# 01_MAIN.net
KiCad netlist of a schematic drawn in Altium Designer
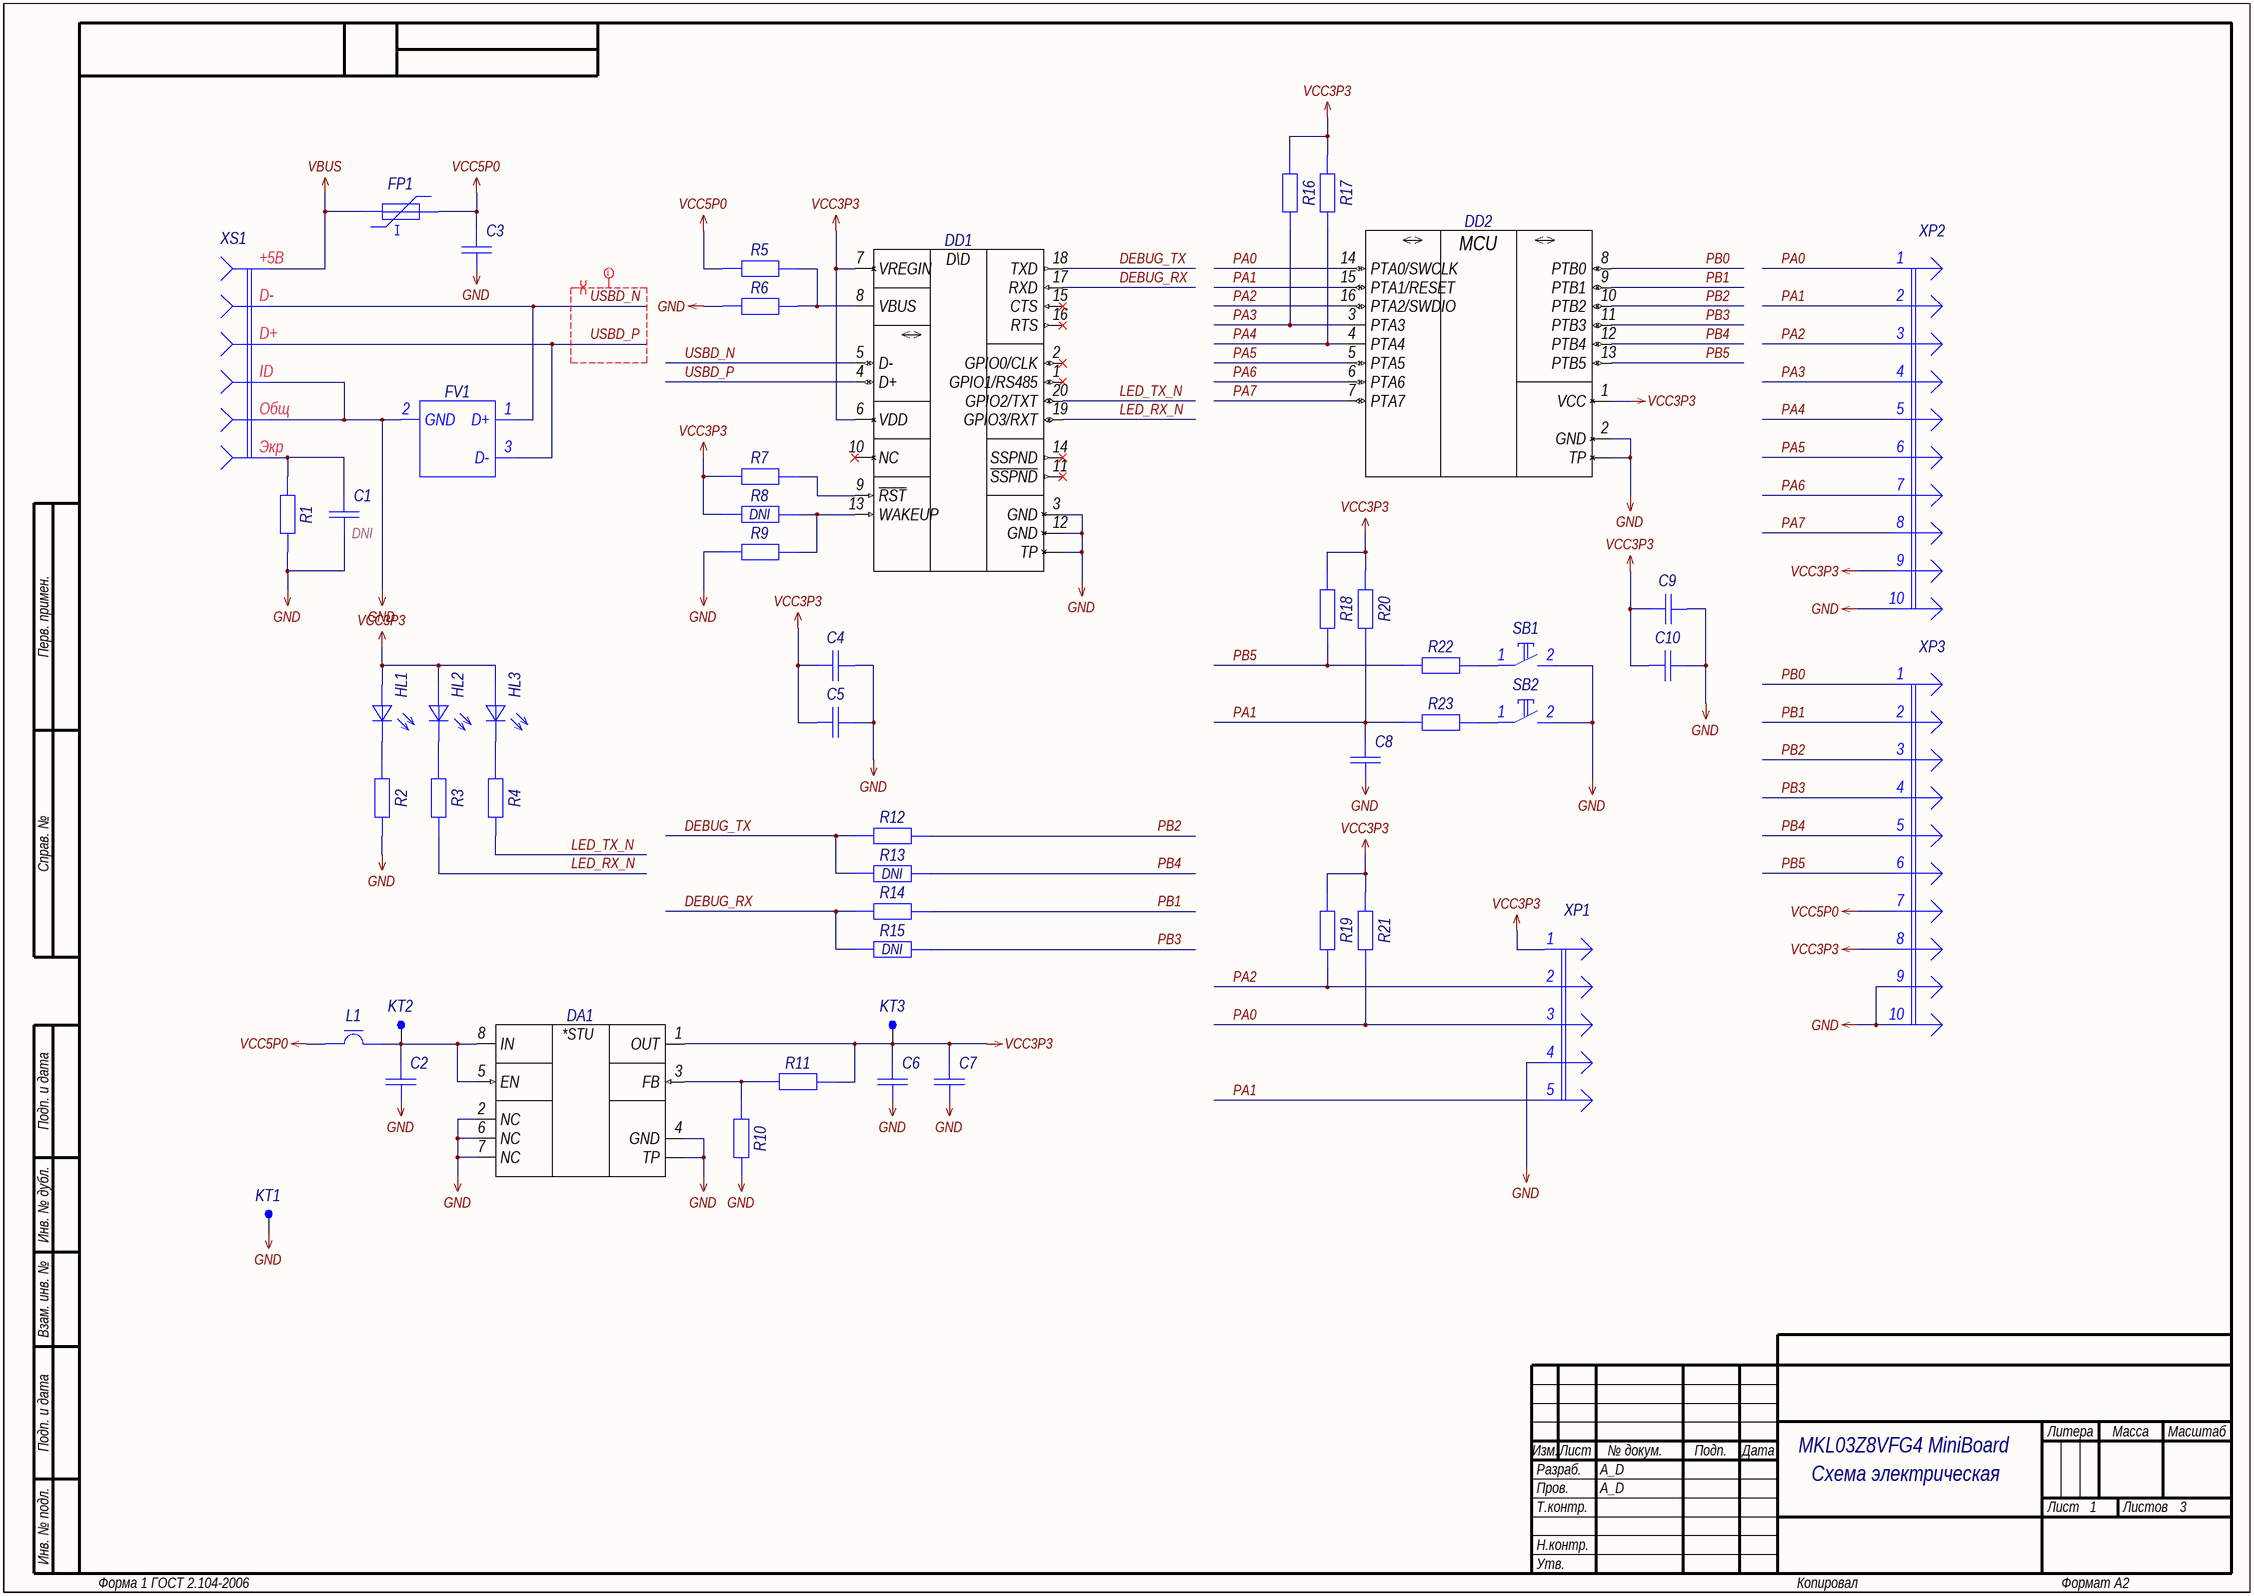
[diagram p0: 01_MAIN.SchDoc]

(export (version "E")
  (design (tool "Eeschema 10.0.6"))
  (components
    (comp (ref "C1")
      (value "Capacitor")
      (footprint "C0603_L")
      (fields
        (field (name "PART NUMBER") "GRM188R72A104KA35D")
        (field (name "VOLTAGE") "100V")
        (field (name "TOLERANCE") "±10%")
        (field (name "PUBLISHER") "Andrew Danich")
      )
      (libsource (lib "ADLib") (part "Capacitor"))
    )
    (comp (ref "C2")
      (value "Capacitor")
      (footprint "C0402_L")
      (fields
        (field (name "PART NUMBER") "GRM155R60J475ME87D")
        (field (name "VOLTAGE") "6.3V")
        (field (name "TOLERANCE") "±20%")
        (field (name "PUBLISHER") "Andrew Danich")
      )
      (libsource (lib "ADLib") (part "Capacitor"))
    )
    (comp (ref "C3")
      (value "Capacitor")
      (footprint "C0603_L")
      (fields
        (field (name "PART NUMBER") "GRM188R60J106ME47D")
        (field (name "VOLTAGE") "6.3V")
        (field (name "TOLERANCE") "±20%")
        (field (name "PUBLISHER") "Andrew Danich")
      )
      (libsource (lib "ADLib") (part "Capacitor"))
    )
    (comp (ref "C4")
      (value "Capacitor")
      (footprint "C0402_L")
      (fields
        (field (name "PART NUMBER") "GRM155R60J475ME87D")
        (field (name "VOLTAGE") "6.3V")
        (field (name "TOLERANCE") "±20%")
        (field (name "PUBLISHER") "Andrew Danich")
      )
      (libsource (lib "ADLib") (part "Capacitor"))
    )
    (comp (ref "C5")
      (value "Capacitor")
      (footprint "C0402_L")
      (fields
        (field (name "PART NUMBER") "GRM155R60J475ME87D")
        (field (name "VOLTAGE") "6.3V")
        (field (name "TOLERANCE") "±20%")
        (field (name "PUBLISHER") "Andrew Danich")
      )
      (libsource (lib "ADLib") (part "Capacitor"))
    )
    (comp (ref "C6")
      (value "Capacitor")
      (footprint "C0402_L")
      (fields
        (field (name "PART NUMBER") "GRM155R60J475ME87D")
        (field (name "VOLTAGE") "6.3V")
        (field (name "TOLERANCE") "±20%")
        (field (name "PUBLISHER") "Andrew Danich")
      )
      (libsource (lib "ADLib") (part "Capacitor"))
    )
    (comp (ref "C7")
      (value "Capacitor")
      (footprint "C0402_L")
      (fields
        (field (name "PART NUMBER") "GRM155R60J475ME87D")
        (field (name "VOLTAGE") "6.3V")
        (field (name "TOLERANCE") "±20%")
        (field (name "PUBLISHER") "Andrew Danich")
      )
      (libsource (lib "ADLib") (part "Capacitor"))
    )
    (comp (ref "C8")
      (value "Capacitor")
      (footprint "C0402_L")
      (fields
        (field (name "PART NUMBER") "GCM155R71C104KA55D")
        (field (name "VOLTAGE") "16V")
        (field (name "TOLERANCE") "±10%")
        (field (name "PUBLISHER") "Andrew Danich")
      )
      (libsource (lib "ADLib") (part "Capacitor"))
    )
    (comp (ref "C9")
      (value "Capacitor")
      (footprint "C0402_L")
      (fields
        (field (name "PART NUMBER") "GRM155C71A105KE11D")
        (field (name "VOLTAGE") "10V")
        (field (name "TOLERANCE") "±10%")
        (field (name "PUBLISHER") "Andrew Danich")
      )
      (libsource (lib "ADLib") (part "Capacitor"))
    )
    (comp (ref "C10")
      (value "Capacitor")
      (footprint "C0402_L")
      (fields
        (field (name "PART NUMBER") "GCM155R71C104KA55D")
        (field (name "VOLTAGE") "16V")
        (field (name "TOLERANCE") "±10%")
        (field (name "PUBLISHER") "Andrew Danich")
      )
      (libsource (lib "ADLib") (part "Capacitor"))
    )
    (comp (ref "DA1")
      (value "TPS73701DRB")
      (footprint "VSON-8_065P300X300X100_N")
      (fields
        (field (name "PART NUMBER") "TPS73701DRBR")
        (field (name "MANUFACTURER") "Texas Instruments")
        (field (name "PUBLISHER") "Andrew Danich")
      )
      (libsource (lib "ADLib") (part "TPS73701DRB"))
    )
    (comp (ref "DD1")
      (value "CP2102N-xxx-GQFN20")
      (footprint "QFN-20_050P300X300X080_N")
      (fields
        (field (name "PART NUMBER") "CP2102N-A01-GQFN20")
        (field (name "MANUFACTURER") "Silicon Labs")
        (field (name "PUBLISHER") "Andrew Danich")
      )
      (libsource (lib "ADLib") (part "CP2102N-xxx-GQFN20"))
    )
    (comp (ref "DD2")
      (value "MKL03ZxxVFG4-Series")
      (footprint "HUQFN-16_050P300X300X065_N")
      (fields
        (field (name "PART NUMBER") "MKL03Z8VFG4")
        (field (name "MANUFACTURER") "NXP Semiconductors")
        (field (name "PUBLISHER") "Andrew Danich")
      )
      (libsource (lib "ADLib") (part "MKL03ZxxVFG4-Series"))
    )
    (comp (ref "FP1")
      (value "Fuse_PTC")
      (footprint "F0603_L")
      (fields (field (name "PART NUMBER") "0603L100SLYR") (field (name "MANUFACTURER") "Littelfuse"))
      (libsource (lib "ADLib") (part "Fuse_PTC"))
    )
    (comp (ref "FV1")
      (value "TPD2EUSB30DRT")
      (footprint "SOT-3_070P100X080X050_N")
      (fields (field (name "MANUFACTURER") "Texas Instruments") (field (name "PUBLISHER") "Andrew Danich"))
      (libsource (lib "ADLib") (part "TPD2EUSB30DRT"))
    )
    (comp (ref "HL1")
      (value "~")
      (footprint "LD0402_L")
      (fields
        (field (name "PART NUMBER") "KPHHS-1005QBC-D-V")
        (field (name "MANUFACTURER") "Kingbright")
        (field (name "PUBLISHER") "Andrew Danich")
      )
      (libsource (lib "ADLib") (part "Led-1"))
    )
    (comp (ref "HL2")
      (value "~")
      (footprint "LD0402_L")
      (fields
        (field (name "PART NUMBER") "KPHHS-1005CGCK")
        (field (name "MANUFACTURER") "Kingbright")
        (field (name "PUBLISHER") "Andrew Danich")
      )
      (libsource (lib "ADLib") (part "Led-1"))
    )
    (comp (ref "HL3")
      (value "~")
      (footprint "LD0402_L")
      (fields
        (field (name "PART NUMBER") "KPHHS-1005SURCK")
        (field (name "MANUFACTURER") "Kingbright")
        (field (name "PUBLISHER") "Andrew Danich")
      )
      (libsource (lib "ADLib") (part "Led-1"))
    )
    (comp (ref "KT1")
      (value "Text")
      (footprint "TP-SMT-R-0.8mm")
      (fields (field (name "PART NUMBER") "TestPoint-SMT-GND") (field (name "PUBLISHER") "Andrew Danich"))
      (libsource (lib "ADLib") (part "TP-S-1"))
    )
    (comp (ref "KT2")
      (value "Text")
      (footprint "TP-SMT-C-0.5mm")
      (fields (field (name "PART NUMBER") "TestPoint-SMT") (field (name "PUBLISHER") "Andrew Danich"))
      (libsource (lib "ADLib") (part "TP-S-1"))
    )
    (comp (ref "KT3")
      (value "Text")
      (footprint "TP-SMT-C-0.5mm")
      (fields (field (name "PART NUMBER") "TestPoint-SMT") (field (name "PUBLISHER") "Andrew Danich"))
      (libsource (lib "ADLib") (part "TP-S-1"))
    )
    (comp (ref "L1")
      (value "FerriteBead")
      (footprint "L0402_L")
      (fields
        (field (name "PART NUMBER") "BLM15PD121SN1D")
        (field (name "TOLERANCE") "±25%")
        (field (name "MANUFACTURER") "Murata")
        (field (name "PUBLISHER") "Andrew Danich")
      )
      (libsource (lib "ADLib") (part "FerriteBead"))
    )
    (comp (ref "R1")
      (value "Resistor")
      (footprint "R0603_L")
      (fields
        (field (name "PART NUMBER") "RC0603JR-070R")
        (field (name "TOLERANCE") "±5%")
        (field (name "MANUFACTURER") "Yageo")
        (field (name "PUBLISHER") "Andrew Danich")
      )
      (libsource (lib "ADLib") (part "Resistor"))
    )
    (comp (ref "R2")
      (value "Resistor")
      (footprint "R0402_L")
      (fields
        (field (name "PART NUMBER") "RC0402JR-071KL")
        (field (name "TOLERANCE") "±5%")
        (field (name "MANUFACTURER") "Yageo")
        (field (name "PUBLISHER") "Andrew Danich")
      )
      (libsource (lib "ADLib") (part "Resistor"))
    )
    (comp (ref "R3")
      (value "Resistor")
      (footprint "R0402_L")
      (fields
        (field (name "PART NUMBER") "RC0402JR-071KL")
        (field (name "TOLERANCE") "±5%")
        (field (name "MANUFACTURER") "Yageo")
        (field (name "PUBLISHER") "Andrew Danich")
      )
      (libsource (lib "ADLib") (part "Resistor"))
    )
    (comp (ref "R4")
      (value "Resistor")
      (footprint "R0402_L")
      (fields
        (field (name "PART NUMBER") "RC0402JR-071KL")
        (field (name "TOLERANCE") "±5%")
        (field (name "MANUFACTURER") "Yageo")
        (field (name "PUBLISHER") "Andrew Danich")
      )
      (libsource (lib "ADLib") (part "Resistor"))
    )
    (comp (ref "R5")
      (value "Resistor")
      (footprint "R0402_L")
      (fields
        (field (name "PART NUMBER") "RC0402FR-0722K1L")
        (field (name "TOLERANCE") "±1%")
        (field (name "MANUFACTURER") "Yageo")
        (field (name "PUBLISHER") "Andrew Danich")
      )
      (libsource (lib "ADLib") (part "Resistor"))
    )
    (comp (ref "R6")
      (value "Resistor")
      (footprint "R0402_L")
      (fields
        (field (name "PART NUMBER") "RC0402FR-0747KL")
        (field (name "TOLERANCE") "±1%")
        (field (name "MANUFACTURER") "Yageo")
        (field (name "PUBLISHER") "Andrew Danich")
      )
      (libsource (lib "ADLib") (part "Resistor"))
    )
    (comp (ref "R7")
      (value "Resistor")
      (footprint "R0402_L")
      (fields
        (field (name "PART NUMBER") "RC0402JR-0710KL")
        (field (name "TOLERANCE") "±5%")
        (field (name "MANUFACTURER") "Yageo")
        (field (name "PUBLISHER") "Andrew Danich")
      )
      (libsource (lib "ADLib") (part "Resistor"))
    )
    (comp (ref "R8")
      (value "Resistor")
      (footprint "R0402_L")
      (fields
        (field (name "PART NUMBER") "RC0402JR-0710KL")
        (field (name "TOLERANCE") "±5%")
        (field (name "MANUFACTURER") "Yageo")
        (field (name "PUBLISHER") "Andrew Danich")
      )
      (libsource (lib "ADLib") (part "Resistor"))
    )
    (comp (ref "R9")
      (value "Resistor")
      (footprint "R0402_L")
      (fields
        (field (name "PART NUMBER") "RC0402JR-070RL")
        (field (name "TOLERANCE") "±5%")
        (field (name "MANUFACTURER") "Yageo")
        (field (name "PUBLISHER") "Andrew Danich")
      )
      (libsource (lib "ADLib") (part "Resistor"))
    )
    (comp (ref "R10")
      (value "Resistor")
      (footprint "R0402_L")
      (fields
        (field (name "PART NUMBER") "RC0402FR-0712KL")
        (field (name "TOLERANCE") "±1%")
        (field (name "MANUFACTURER") "Yageo")
        (field (name "PUBLISHER") "Andrew Danich")
      )
      (libsource (lib "ADLib") (part "Resistor"))
    )
    (comp (ref "R11")
      (value "Resistor")
      (footprint "R0402_L")
      (fields
        (field (name "PART NUMBER") "RC0402FR-0722K1L")
        (field (name "TOLERANCE") "±1%")
        (field (name "MANUFACTURER") "Yageo")
        (field (name "PUBLISHER") "Andrew Danich")
      )
      (libsource (lib "ADLib") (part "Resistor"))
    )
    (comp (ref "R12")
      (value "Resistor")
      (footprint "R0402_L")
      (fields
        (field (name "PART NUMBER") "RC0402JR-070RL")
        (field (name "TOLERANCE") "±5%")
        (field (name "MANUFACTURER") "Yageo")
        (field (name "PUBLISHER") "Andrew Danich")
      )
      (libsource (lib "ADLib") (part "Resistor"))
    )
    (comp (ref "R13")
      (value "Resistor")
      (footprint "R0402_L")
      (fields
        (field (name "PART NUMBER") "RC0402JR-070RL")
        (field (name "TOLERANCE") "±5%")
        (field (name "MANUFACTURER") "Yageo")
        (field (name "PUBLISHER") "Andrew Danich")
      )
      (libsource (lib "ADLib") (part "Resistor"))
    )
    (comp (ref "R14")
      (value "Resistor")
      (footprint "R0402_L")
      (fields
        (field (name "PART NUMBER") "RC0402JR-070RL")
        (field (name "TOLERANCE") "±5%")
        (field (name "MANUFACTURER") "Yageo")
        (field (name "PUBLISHER") "Andrew Danich")
      )
      (libsource (lib "ADLib") (part "Resistor"))
    )
    (comp (ref "R15")
      (value "Resistor")
      (footprint "R0402_L")
      (fields
        (field (name "PART NUMBER") "RC0402JR-070RL")
        (field (name "TOLERANCE") "±5%")
        (field (name "MANUFACTURER") "Yageo")
        (field (name "PUBLISHER") "Andrew Danich")
      )
      (libsource (lib "ADLib") (part "Resistor"))
    )
    (comp (ref "R16")
      (value "Resistor")
      (footprint "R0402_L")
      (fields
        (field (name "PART NUMBER") "RC0402JR-074K7L")
        (field (name "TOLERANCE") "±5%")
        (field (name "MANUFACTURER") "Yageo")
        (field (name "PUBLISHER") "Andrew Danich")
      )
      (libsource (lib "ADLib") (part "Resistor"))
    )
    (comp (ref "R17")
      (value "Resistor")
      (footprint "R0402_L")
      (fields
        (field (name "PART NUMBER") "RC0402JR-074K7L")
        (field (name "TOLERANCE") "±5%")
        (field (name "MANUFACTURER") "Yageo")
        (field (name "PUBLISHER") "Andrew Danich")
      )
      (libsource (lib "ADLib") (part "Resistor"))
    )
    (comp (ref "R18")
      (value "Resistor")
      (footprint "R0402_L")
      (fields
        (field (name "PART NUMBER") "RC0402JR-0710KL")
        (field (name "TOLERANCE") "±5%")
        (field (name "MANUFACTURER") "Yageo")
        (field (name "PUBLISHER") "Andrew Danich")
      )
      (libsource (lib "ADLib") (part "Resistor"))
    )
    (comp (ref "R19")
      (value "Resistor")
      (footprint "R0402_L")
      (fields
        (field (name "PART NUMBER") "RC0402JR-0710KL")
        (field (name "TOLERANCE") "±5%")
        (field (name "MANUFACTURER") "Yageo")
        (field (name "PUBLISHER") "Andrew Danich")
      )
      (libsource (lib "ADLib") (part "Resistor"))
    )
    (comp (ref "R20")
      (value "Resistor")
      (footprint "R0402_L")
      (fields
        (field (name "PART NUMBER") "RC0402JR-0710KL")
        (field (name "TOLERANCE") "±5%")
        (field (name "MANUFACTURER") "Yageo")
        (field (name "PUBLISHER") "Andrew Danich")
      )
      (libsource (lib "ADLib") (part "Resistor"))
    )
    (comp (ref "R21")
      (value "Resistor")
      (footprint "R0402_L")
      (fields
        (field (name "PART NUMBER") "RC0402JR-0710KL")
        (field (name "TOLERANCE") "±5%")
        (field (name "MANUFACTURER") "Yageo")
        (field (name "PUBLISHER") "Andrew Danich")
      )
      (libsource (lib "ADLib") (part "Resistor"))
    )
    (comp (ref "R22")
      (value "Resistor")
      (footprint "R0402_L")
      (fields
        (field (name "PART NUMBER") "RC0402JR-07100RL")
        (field (name "TOLERANCE") "±5%")
        (field (name "MANUFACTURER") "Yageo")
        (field (name "PUBLISHER") "Andrew Danich")
      )
      (libsource (lib "ADLib") (part "Resistor"))
    )
    (comp (ref "R23")
      (value "Resistor")
      (footprint "R0402_L")
      (fields
        (field (name "PART NUMBER") "RC0402JR-07100RL")
        (field (name "TOLERANCE") "±5%")
        (field (name "MANUFACTURER") "Yageo")
        (field (name "PUBLISHER") "Andrew Danich")
      )
      (libsource (lib "ADLib") (part "Resistor"))
    )
    (comp (ref "SB1")
      (value "RESET")
      (footprint "IT-1185AP")
      (fields (field (name "PART NUMBER") "IT-1185AP") (field (name "PUBLISHER") "Andrew Danich"))
      (libsource (lib "ADLib") (part "BT-01x-01p"))
    )
    (comp (ref "SB2")
      (value "NMI")
      (footprint "IT-1185AP")
      (fields (field (name "PART NUMBER") "IT-1185AP") (field (name "PUBLISHER") "Andrew Danich"))
      (libsource (lib "ADLib") (part "BT-01x-01p"))
    )
    (comp (ref "XP1")
      (value "Text")
      (footprint "PLS-5")
      (fields (field (name "PART NUMBER") "PLS-5") (field (name "PUBLISHER") "Andrew Danich"))
      (libsource (lib "ADLib") (part "Con-5-M"))
    )
    (comp (ref "XP2")
      (value "PA")
      (footprint "PLS-10")
      (fields (field (name "PART NUMBER") "PLS-10") (field (name "PUBLISHER") "Andrew Danich"))
      (libsource (lib "ADLib") (part "Con-10-M"))
    )
    (comp (ref "XP3")
      (value "PB")
      (footprint "PLS-10")
      (fields (field (name "PART NUMBER") "PLS-10") (field (name "PUBLISHER") "Andrew Danich"))
      (libsource (lib "ADLib") (part "Con-10-M"))
    )
    (comp (ref "XS1")
      (value "USB")
      (footprint "1981568-1")
      (fields
        (field (name "PART NUMBER") "1981568-1")
        (field (name "MANUFACTURER") "TE Connectivity")
        (field (name "PUBLISHER") "Andrew Danich")
      )
      (libsource (lib "ADLib") (part "Con-6-F-USB"))
    )
  )
  (nets
    (net (code "1") (name "/DEBUG_RX") (class "Default")
      (node (ref "DD1") (pin "17") (pinfunction "RXD_17") (pintype "input"))
      (node (ref "R14") (pin "1") (pinfunction "1_1") (pintype "passive"))
      (node (ref "R15") (pin "1") (pinfunction "1_1") (pintype "passive"))
    )
    (net (code "2") (name "/DEBUG_TX") (class "Default")
      (node (ref "DD1") (pin "18") (pinfunction "TXD_18") (pintype "output"))
      (node (ref "R12") (pin "1") (pinfunction "1_1") (pintype "passive"))
      (node (ref "R13") (pin "1") (pinfunction "1_1") (pintype "passive"))
    )
    (net (code "3") (name "/LED_RX_N") (class "Default")
      (node (ref "DD1") (pin "19") (pinfunction "GPIO3/RXT_19") (pintype "bidirectional"))
      (node (ref "R3") (pin "1") (pinfunction "1_1") (pintype "passive"))
    )
    (net (code "4") (name "/LED_TX_N") (class "Default")
      (node (ref "DD1") (pin "20") (pinfunction "GPIO2/TXT_20") (pintype "bidirectional"))
      (node (ref "R4") (pin "1") (pinfunction "1_1") (pintype "passive"))
    )
    (net (code "5") (name "/PA0") (class "Default")
      (node (ref "DD2") (pin "14") (pinfunction "PTA0/SWCLK_14") (pintype "bidirectional"))
      (node (ref "R21") (pin "2") (pinfunction "2_2") (pintype "passive"))
      (node (ref "XP1") (pin "3") (pintype "passive"))
      (node (ref "XP2") (pin "1") (pintype "passive"))
    )
    (net (code "6") (name "/PA1") (class "Default")
      (node (ref "C8") (pin "1") (pinfunction "1_1") (pintype "passive"))
      (node (ref "DD2") (pin "15") (pinfunction "PTA1/RESET_15") (pintype "bidirectional"))
      (node (ref "R20") (pin "2") (pinfunction "2_2") (pintype "passive"))
      (node (ref "R23") (pin "1") (pinfunction "1_1") (pintype "passive"))
      (node (ref "XP1") (pin "5") (pintype "passive"))
      (node (ref "XP2") (pin "2") (pintype "passive"))
    )
    (net (code "7") (name "/PA2") (class "Default")
      (node (ref "DD2") (pin "16") (pinfunction "PTA2/SWDIO_16") (pintype "bidirectional"))
      (node (ref "R19") (pin "2") (pinfunction "2_2") (pintype "passive"))
      (node (ref "XP1") (pin "2") (pintype "passive"))
      (node (ref "XP2") (pin "3") (pintype "passive"))
    )
    (net (code "8") (name "/PA3") (class "Default")
      (node (ref "DD2") (pin "3") (pinfunction "PTA3_3") (pintype "open_collector"))
      (node (ref "R16") (pin "1") (pinfunction "1_1") (pintype "passive"))
      (node (ref "XP2") (pin "4") (pintype "passive"))
    )
    (net (code "9") (name "/PA4") (class "Default")
      (node (ref "DD2") (pin "4") (pinfunction "PTA4_4") (pintype "open_collector"))
      (node (ref "R17") (pin "1") (pinfunction "1_1") (pintype "passive"))
      (node (ref "XP2") (pin "5") (pintype "passive"))
    )
    (net (code "10") (name "/PA5") (class "Default")
      (node (ref "DD2") (pin "5") (pinfunction "PTA5_5") (pintype "bidirectional"))
      (node (ref "XP2") (pin "6") (pintype "passive"))
    )
    (net (code "11") (name "/PA6") (class "Default")
      (node (ref "DD2") (pin "6") (pinfunction "PTA6_6") (pintype "bidirectional"))
      (node (ref "XP2") (pin "7") (pintype "passive"))
    )
    (net (code "12") (name "/PA7") (class "Default")
      (node (ref "DD2") (pin "7") (pinfunction "PTA7_7") (pintype "bidirectional"))
      (node (ref "XP2") (pin "8") (pintype "passive"))
    )
    (net (code "13") (name "/PB0") (class "Default")
      (node (ref "DD2") (pin "8") (pinfunction "PTB0_8") (pintype "bidirectional"))
      (node (ref "XP3") (pin "1") (pintype "passive"))
    )
    (net (code "14") (name "/PB1") (class "Default")
      (node (ref "DD2") (pin "9") (pinfunction "PTB1_9") (pintype "bidirectional"))
      (node (ref "R14") (pin "2") (pinfunction "2_2") (pintype "passive"))
      (node (ref "XP3") (pin "2") (pintype "passive"))
    )
    (net (code "15") (name "/PB2") (class "Default")
      (node (ref "DD2") (pin "10") (pinfunction "PTB2_10") (pintype "bidirectional"))
      (node (ref "R12") (pin "2") (pinfunction "2_2") (pintype "passive"))
      (node (ref "XP3") (pin "3") (pintype "passive"))
    )
    (net (code "16") (name "/PB3") (class "Default")
      (node (ref "DD2") (pin "11") (pinfunction "PTB3_11") (pintype "bidirectional"))
      (node (ref "R15") (pin "2") (pinfunction "2_2") (pintype "passive"))
      (node (ref "XP3") (pin "4") (pintype "passive"))
    )
    (net (code "17") (name "/PB4") (class "Default")
      (node (ref "DD2") (pin "12") (pinfunction "PTB4_12") (pintype "bidirectional"))
      (node (ref "R13") (pin "2") (pinfunction "2_2") (pintype "passive"))
      (node (ref "XP3") (pin "5") (pintype "passive"))
    )
    (net (code "18") (name "/PB5") (class "Default")
      (node (ref "DD2") (pin "13") (pinfunction "PTB5_13") (pintype "bidirectional"))
      (node (ref "R18") (pin "2") (pinfunction "2_2") (pintype "passive"))
      (node (ref "R22") (pin "1") (pinfunction "1_1") (pintype "passive"))
      (node (ref "XP3") (pin "6") (pintype "passive"))
    )
    (net (code "19") (name "/USBD_N") (class "Default")
      (node (ref "DD1") (pin "5") (pinfunction "D-_5") (pintype "bidirectional"))
      (node (ref "FV1") (pin "1") (pinfunction "D+_1") (pintype "passive"))
      (node (ref "XS1") (pin "2") (pintype "passive"))
    )
    (net (code "20") (name "/USBD_P") (class "Default")
      (node (ref "DD1") (pin "4") (pinfunction "D+_4") (pintype "bidirectional"))
      (node (ref "FV1") (pin "3") (pinfunction "D-_3") (pintype "passive"))
      (node (ref "XS1") (pin "3") (pintype "passive"))
    )
    (net (code "21") (name "GND") (class "Default")
      (node (ref "C1") (pin "1") (pinfunction "1_1") (pintype "passive"))
      (node (ref "C10") (pin "1") (pinfunction "1_1") (pintype "passive"))
      (node (ref "C2") (pin "1") (pinfunction "1_1") (pintype "passive"))
      (node (ref "C3") (pin "1") (pinfunction "1_1") (pintype "passive"))
      (node (ref "C4") (pin "1") (pinfunction "1_1") (pintype "passive"))
      (node (ref "C5") (pin "1") (pinfunction "1_1") (pintype "passive"))
      (node (ref "C6") (pin "1") (pinfunction "1_1") (pintype "passive"))
      (node (ref "C7") (pin "1") (pinfunction "1_1") (pintype "passive"))
      (node (ref "C8") (pin "2") (pinfunction "2_2") (pintype "passive"))
      (node (ref "C9") (pin "2") (pinfunction "2_2") (pintype "passive"))
      (node (ref "DA1") (pin "2") (pinfunction "NC_2") (pintype "passive"))
      (node (ref "DA1") (pin "4") (pinfunction "GND_4") (pintype "power_in"))
      (node (ref "DA1") (pin "6") (pinfunction "NC_6") (pintype "passive"))
      (node (ref "DA1") (pin "7") (pinfunction "NC_7") (pintype "passive"))
      (node (ref "DA1") (pin "TP") (pinfunction "TP_TP") (pintype "passive"))
      (node (ref "DD1") (pin "12") (pinfunction "GND_12") (pintype "power_in"))
      (node (ref "DD1") (pin "3") (pinfunction "GND_3") (pintype "power_in"))
      (node (ref "DD1") (pin "TP") (pinfunction "TP_TP") (pintype "power_in"))
      (node (ref "DD2") (pin "2") (pinfunction "GND_2") (pintype "power_in"))
      (node (ref "DD2") (pin "TP") (pinfunction "TP_TP") (pintype "power_in"))
      (node (ref "FV1") (pin "2") (pinfunction "GND_2") (pintype "passive"))
      (node (ref "KT1") (pin "1") (pinfunction "1_1") (pintype "passive"))
      (node (ref "R1") (pin "1") (pinfunction "1_1") (pintype "passive"))
      (node (ref "R10") (pin "1") (pinfunction "1_1") (pintype "passive"))
      (node (ref "R2") (pin "1") (pinfunction "1_1") (pintype "passive"))
      (node (ref "R6") (pin "1") (pinfunction "1_1") (pintype "passive"))
      (node (ref "R9") (pin "1") (pinfunction "1_1") (pintype "passive"))
      (node (ref "SB1") (pin "2") (pintype "passive"))
      (node (ref "SB2") (pin "2") (pintype "passive"))
      (node (ref "XP1") (pin "4") (pintype "passive"))
      (node (ref "XP2") (pin "10") (pintype "passive"))
      (node (ref "XP3") (pin "10") (pintype "passive"))
      (node (ref "XP3") (pin "9") (pintype "passive"))
      (node (ref "XS1") (pin "4") (pintype "passive"))
      (node (ref "XS1") (pin "5") (pintype "passive"))
    )
    (net (code "22") (name "Net-(C1-Pad2)") (class "Default")
      (node (ref "C1") (pin "2") (pinfunction "2_2") (pintype "passive"))
      (node (ref "R1") (pin "2") (pinfunction "2_2") (pintype "passive"))
      (node (ref "XS1") (pin "6") (pintype "passive"))
    )
    (net (code "23") (name "Net-(DA1-EN)") (class "Default")
      (node (ref "C2") (pin "2") (pinfunction "2_2") (pintype "passive"))
      (node (ref "DA1") (pin "5") (pinfunction "EN_5") (pintype "input"))
      (node (ref "DA1") (pin "8") (pinfunction "IN_8") (pintype "power_in"))
      (node (ref "KT2") (pin "1") (pinfunction "1_1") (pintype "passive"))
      (node (ref "L1") (pin "2") (pinfunction "2_2") (pintype "passive"))
    )
    (net (code "24") (name "Net-(DA1-FB)") (class "Default")
      (node (ref "DA1") (pin "3") (pinfunction "FB_3") (pintype "input"))
      (node (ref "R10") (pin "2") (pinfunction "2_2") (pintype "passive"))
      (node (ref "R11") (pin "1") (pinfunction "1_1") (pintype "passive"))
    )
    (net (code "25") (name "Net-(DD1-VBUS)") (class "Default")
      (node (ref "DD1") (pin "8") (pinfunction "VBUS_8") (pintype "power_in"))
      (node (ref "R5") (pin "2") (pinfunction "2_2") (pintype "passive"))
      (node (ref "R6") (pin "2") (pinfunction "2_2") (pintype "passive"))
    )
    (net (code "26") (name "Net-(DD1-WAKEUP)") (class "Default")
      (node (ref "DD1") (pin "13") (pinfunction "WAKEUP_13") (pintype "input"))
      (node (ref "R8") (pin "1") (pinfunction "1_1") (pintype "passive"))
      (node (ref "R9") (pin "2") (pinfunction "2_2") (pintype "passive"))
    )
    (net (code "27") (name "Net-(DD1-~{RST})") (class "Default")
      (node (ref "DD1") (pin "9") (pinfunction "~{RST}_9") (pintype "input"))
      (node (ref "R7") (pin "1") (pinfunction "1_1") (pintype "passive"))
    )
    (net (code "28") (name "Net-(HL1-К)") (class "Default")
      (node (ref "HL1") (pin "2") (pinfunction "К_2") (pintype "passive"))
      (node (ref "R2") (pin "2") (pinfunction "2_2") (pintype "passive"))
    )
    (net (code "29") (name "Net-(HL2-К)") (class "Default")
      (node (ref "HL2") (pin "2") (pinfunction "К_2") (pintype "passive"))
      (node (ref "R3") (pin "2") (pinfunction "2_2") (pintype "passive"))
    )
    (net (code "30") (name "Net-(HL3-К)") (class "Default")
      (node (ref "HL3") (pin "2") (pinfunction "К_2") (pintype "passive"))
      (node (ref "R4") (pin "2") (pinfunction "2_2") (pintype "passive"))
    )
    (net (code "31") (name "Net-(R22-Pad2)") (class "Default")
      (node (ref "R22") (pin "2") (pinfunction "2_2") (pintype "passive"))
      (node (ref "SB1") (pin "1") (pintype "passive"))
    )
    (net (code "32") (name "Net-(R23-Pad2)") (class "Default")
      (node (ref "R23") (pin "2") (pinfunction "2_2") (pintype "passive"))
      (node (ref "SB2") (pin "1") (pintype "passive"))
    )
    (net (code "33") (name "VBUS") (class "Default")
      (node (ref "FP1") (pin "1") (pinfunction "1_1") (pintype "passive"))
      (node (ref "XS1") (pin "1") (pintype "passive"))
    )
    (net (code "34") (name "VCC3P3") (class "Default")
      (node (ref "C10") (pin "2") (pinfunction "2_2") (pintype "passive"))
      (node (ref "C4") (pin "2") (pinfunction "2_2") (pintype "passive"))
      (node (ref "C5") (pin "2") (pinfunction "2_2") (pintype "passive"))
      (node (ref "C6") (pin "2") (pinfunction "2_2") (pintype "passive"))
      (node (ref "C7") (pin "2") (pinfunction "2_2") (pintype "passive"))
      (node (ref "C9") (pin "1") (pinfunction "1_1") (pintype "passive"))
      (node (ref "DA1") (pin "1") (pinfunction "OUT_1") (pintype "power_in"))
      (node (ref "DD1") (pin "6") (pinfunction "VDD_6") (pintype "power_in"))
      (node (ref "DD1") (pin "7") (pinfunction "VREGIN_7") (pintype "power_in"))
      (node (ref "DD2") (pin "1") (pinfunction "VCC_1") (pintype "power_in"))
      (node (ref "HL1") (pin "1") (pinfunction "А_1") (pintype "passive"))
      (node (ref "HL2") (pin "1") (pinfunction "А_1") (pintype "passive"))
      (node (ref "HL3") (pin "1") (pinfunction "А_1") (pintype "passive"))
      (node (ref "KT3") (pin "1") (pinfunction "1_1") (pintype "passive"))
      (node (ref "R11") (pin "2") (pinfunction "2_2") (pintype "passive"))
      (node (ref "R16") (pin "2") (pinfunction "2_2") (pintype "passive"))
      (node (ref "R17") (pin "2") (pinfunction "2_2") (pintype "passive"))
      (node (ref "R18") (pin "1") (pinfunction "1_1") (pintype "passive"))
      (node (ref "R19") (pin "1") (pinfunction "1_1") (pintype "passive"))
      (node (ref "R20") (pin "1") (pinfunction "1_1") (pintype "passive"))
      (node (ref "R21") (pin "1") (pinfunction "1_1") (pintype "passive"))
      (node (ref "R7") (pin "2") (pinfunction "2_2") (pintype "passive"))
      (node (ref "R8") (pin "2") (pinfunction "2_2") (pintype "passive"))
      (node (ref "XP1") (pin "1") (pintype "passive"))
      (node (ref "XP2") (pin "9") (pintype "passive"))
      (node (ref "XP3") (pin "8") (pintype "passive"))
    )
    (net (code "35") (name "VCC5P0") (class "Default")
      (node (ref "C3") (pin "2") (pinfunction "2_2") (pintype "passive"))
      (node (ref "FP1") (pin "2") (pinfunction "2_2") (pintype "passive"))
      (node (ref "L1") (pin "1") (pinfunction "1_1") (pintype "passive"))
      (node (ref "R5") (pin "1") (pinfunction "1_1") (pintype "passive"))
      (node (ref "XP3") (pin "7") (pintype "passive"))
    )
    (net (code "36") (name "unconnected-(DD1-CTS-Pad15)") (class "Default")
      (node (ref "DD1") (pin "15") (pinfunction "CTS_15") (pintype "input+no_connect"))
    )
    (net (code "37") (name "unconnected-(DD1-GPIO0{slash}CLK-Pad2)") (class "Default")
      (node (ref "DD1") (pin "2") (pinfunction "GPIO0/CLK_2") (pintype "bidirectional+no_connect"))
    )
    (net (code "38") (name "unconnected-(DD1-GPIO1{slash}RS485-Pad1)") (class "Default")
      (node (ref "DD1") (pin "1") (pinfunction "GPIO1/RS485_1") (pintype "bidirectional+no_connect"))
    )
    (net (code "39") (name "unconnected-(DD1-NC-Pad10)") (class "Default")
      (node (ref "DD1") (pin "10") (pinfunction "NC_10") (pintype "passive+no_connect"))
    )
    (net (code "40") (name "unconnected-(DD1-RTS-Pad16)") (class "Default")
      (node (ref "DD1") (pin "16") (pinfunction "RTS_16") (pintype "output+no_connect"))
    )
    (net (code "41") (name "unconnected-(DD1-SSPND-Pad14)") (class "Default")
      (node (ref "DD1") (pin "14") (pinfunction "SSPND_14") (pintype "output+no_connect"))
    )
    (net (code "42") (name "unconnected-(DD1-~{SSPND}-Pad11)") (class "Default")
      (node (ref "DD1") (pin "11") (pinfunction "~{SSPND}_11") (pintype "output+no_connect"))
    )
  )
)
